# ogranicznik_napiecia.net
KiCad netlist of a schematic drawn in EAGLE
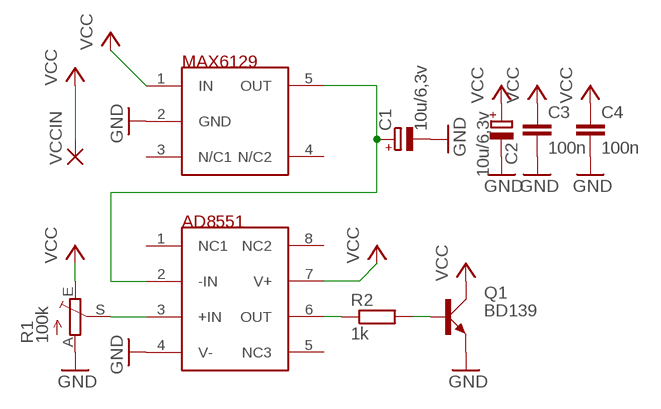
[diagram p0: schematic, sheet 1]

(export (version "E")
  (design (tool "Eeschema 10.0.6"))
  (components
    (comp (ref "C1")
      (value "10u/6,3v")
      (footprint "eagle-import:SMC_B")
      (libsource (lib "eagle-import") (part "CPOL-EUSMCB"))
    )
    (comp (ref "C2")
      (value "10u/6,3v")
      (footprint "eagle-import:SMC_B")
      (libsource (lib "eagle-import") (part "CPOL-EUSMCB"))
    )
    (comp (ref "C3")
      (value "100n")
      (footprint "eagle-import:C0805")
      (libsource (lib "eagle-import") (part "C-EUC0805"))
    )
    (comp (ref "C4")
      (value "100n")
      (footprint "eagle-import:C0805")
      (libsource (lib "eagle-import") (part "C-EUC0805"))
    )
    (comp (ref "Q1")
      (value "BD139")
      (footprint "eagle-import:TO126AV")
      (libsource (lib "eagle-import") (part "BD139"))
    )
    (comp (ref "R1")
      (value "100k")
      (footprint "eagle-import:RJ9W")
      (libsource (lib "eagle-import") (part "TRIM_EU-RJ9W"))
    )
    (comp (ref "R2")
      (value "1k")
      (footprint "eagle-import:M0805")
      (libsource (lib "eagle-import") (part "R-EU_M0805"))
    )
    (comp (ref "U$1")
      (value "AD8551")
      (footprint "eagle-import:SOIC8")
      (libsource (lib "eagle-import") (part "AD8551"))
    )
    (comp (ref "U$2")
      (value "MAX6129")
      (footprint "eagle-import:SOT23-5L")
      (libsource (lib "eagle-import") (part "MAX6129"))
    )
    (comp (ref "VCCIN")
      (value "2,54/0,9")
      (footprint "eagle-import:2,54_0,9")
      (libsource (lib "eagle-import") (part "2,54/0,9"))
    )
  )
  (nets
    (net (code "1") (name "GND") (class "Default")
      (node (ref "C1") (pin "-") (pinfunction "-_-") (pintype "passive"))
      (node (ref "C2") (pin "-") (pinfunction "-_-") (pintype "passive"))
      (node (ref "C3") (pin "2") (pinfunction "2_2") (pintype "passive"))
      (node (ref "C4") (pin "2") (pinfunction "2_2") (pintype "passive"))
      (node (ref "Q1") (pin "E") (pinfunction "E_E") (pintype "passive"))
      (node (ref "R1") (pin "A") (pinfunction "A_A") (pintype "passive"))
      (node (ref "U$1") (pin "4") (pinfunction "V-_4") (pintype "bidirectional"))
      (node (ref "U$2") (pin "2") (pinfunction "GND_2") (pintype "bidirectional"))
    )
    (net (code "2") (name "Net-(Q1-PadB)") (class "Default")
      (node (ref "Q1") (pin "B") (pinfunction "B_B") (pintype "passive"))
      (node (ref "R2") (pin "2") (pinfunction "2_2") (pintype "passive"))
    )
    (net (code "3") (name "Net-(U$1-+IN)") (class "Default")
      (node (ref "R1") (pin "S") (pinfunction "S_S") (pintype "passive"))
      (node (ref "U$1") (pin "3") (pinfunction "+IN_3") (pintype "bidirectional"))
    )
    (net (code "4") (name "Net-(U$1--IN)") (class "Default")
      (node (ref "C1") (pin "+") (pinfunction "+_+") (pintype "passive"))
      (node (ref "U$1") (pin "2") (pinfunction "-IN_2") (pintype "bidirectional"))
      (node (ref "U$2") (pin "5") (pinfunction "OUT_5") (pintype "bidirectional"))
    )
    (net (code "5") (name "Net-(U$1-OUT)") (class "Default")
      (node (ref "R2") (pin "1") (pinfunction "1_1") (pintype "passive"))
      (node (ref "U$1") (pin "6") (pinfunction "OUT_6") (pintype "bidirectional"))
    )
    (net (code "6") (name "VCC") (class "Default")
      (node (ref "C2") (pin "+") (pinfunction "+_+") (pintype "passive"))
      (node (ref "C3") (pin "1") (pinfunction "1_1") (pintype "passive"))
      (node (ref "C4") (pin "1") (pinfunction "1_1") (pintype "passive"))
      (node (ref "Q1") (pin "C") (pinfunction "C_C") (pintype "passive"))
      (node (ref "R1") (pin "E") (pinfunction "E_E") (pintype "passive"))
      (node (ref "U$1") (pin "7") (pinfunction "V+_7") (pintype "bidirectional"))
      (node (ref "U$2") (pin "1") (pinfunction "IN_1") (pintype "bidirectional"))
      (node (ref "VCCIN") (pin "1") (pinfunction "P_1") (pintype "passive"))
    )
    (net (code "7") (name "unconnected-(U$1-NC1-Pad1)") (class "Default")
      (node (ref "U$1") (pin "1") (pinfunction "NC1_1") (pintype "bidirectional"))
    )
    (net (code "8") (name "unconnected-(U$1-NC2-Pad8)") (class "Default")
      (node (ref "U$1") (pin "8") (pinfunction "NC2_8") (pintype "bidirectional"))
    )
    (net (code "9") (name "unconnected-(U$1-NC3-Pad5)") (class "Default")
      (node (ref "U$1") (pin "5") (pinfunction "NC3_5") (pintype "bidirectional"))
    )
    (net (code "10") (name "unconnected-(U$2-N{slash}C1-Pad3)") (class "Default")
      (node (ref "U$2") (pin "3") (pinfunction "N/C1_3") (pintype "bidirectional"))
    )
    (net (code "11") (name "unconnected-(U$2-N{slash}C2-Pad4)") (class "Default")
      (node (ref "U$2") (pin "4") (pinfunction "N/C2_4") (pintype "bidirectional"))
    )
  )
)
